# BMS_MCU.net
KiCad netlist of a schematic drawn in Altium Designer
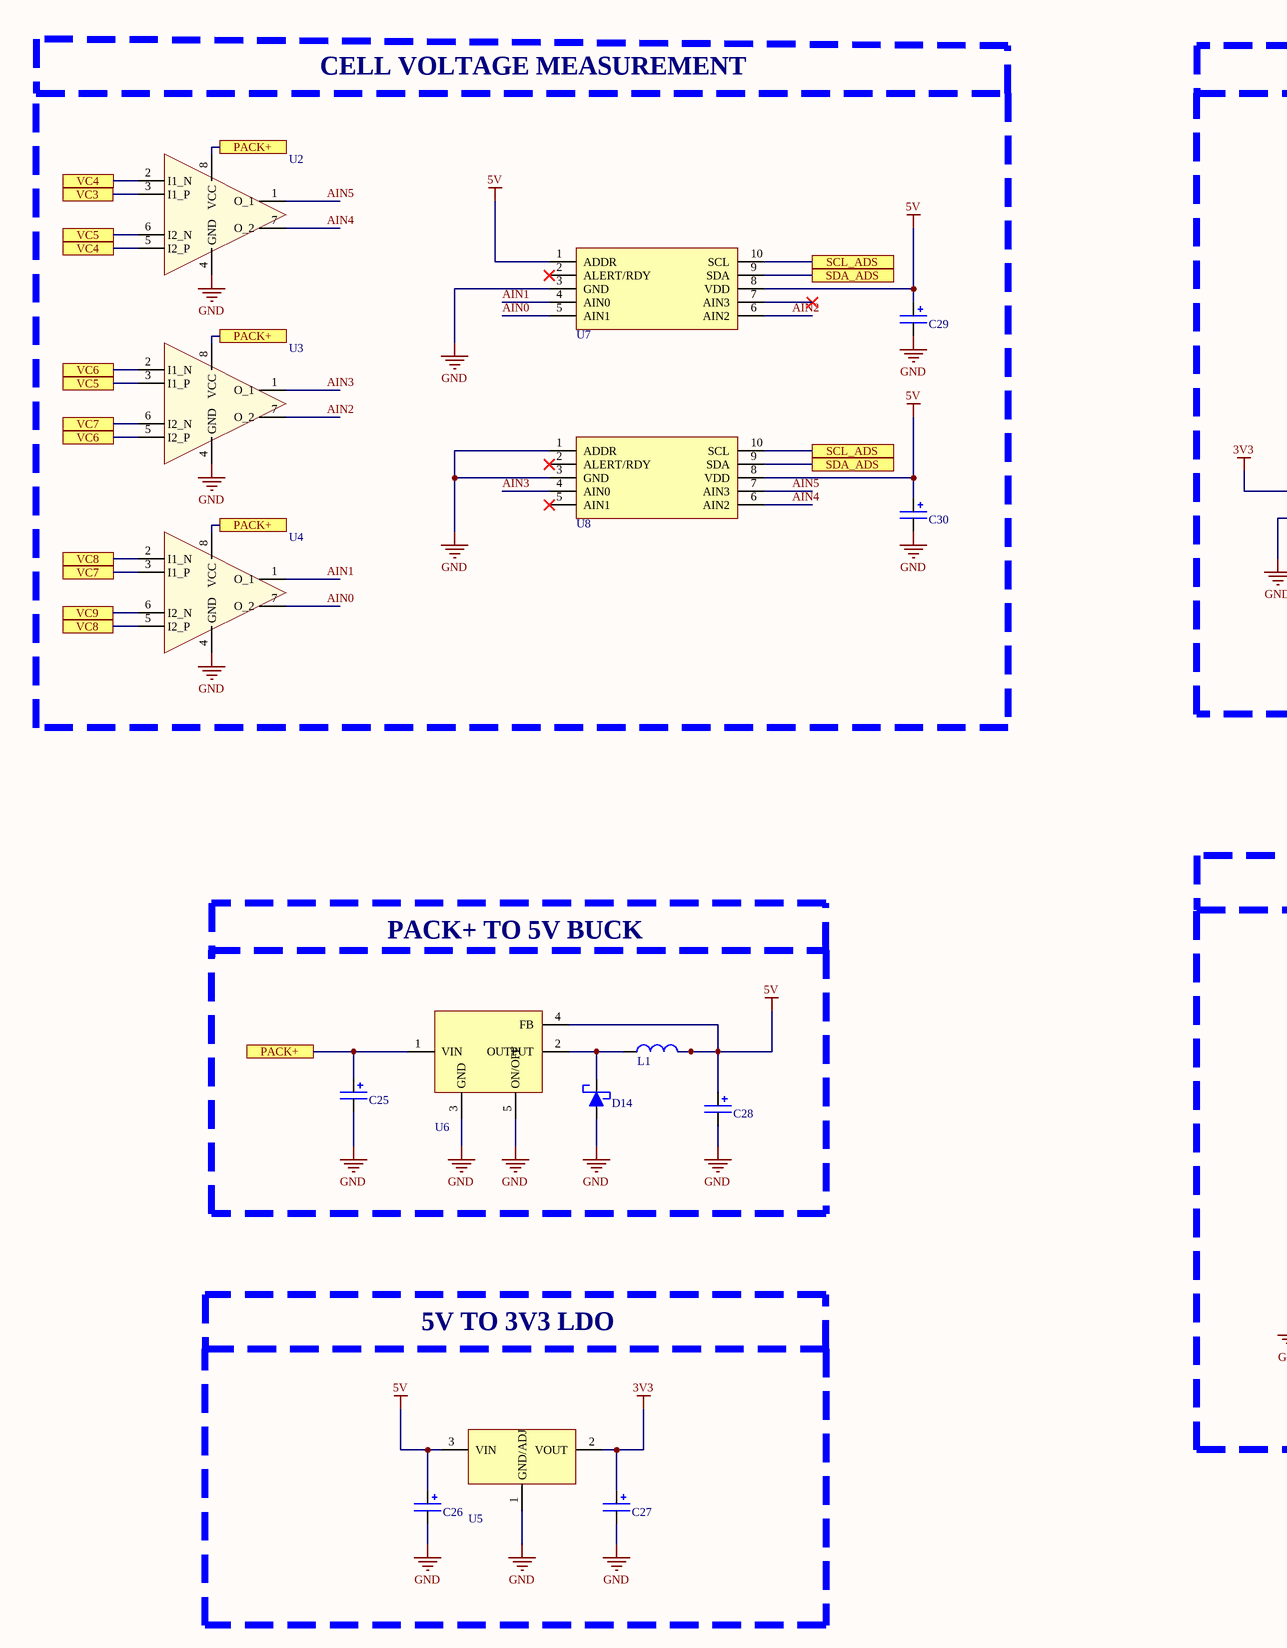
[diagram p0: BMS_MCU.SchDoc, left]
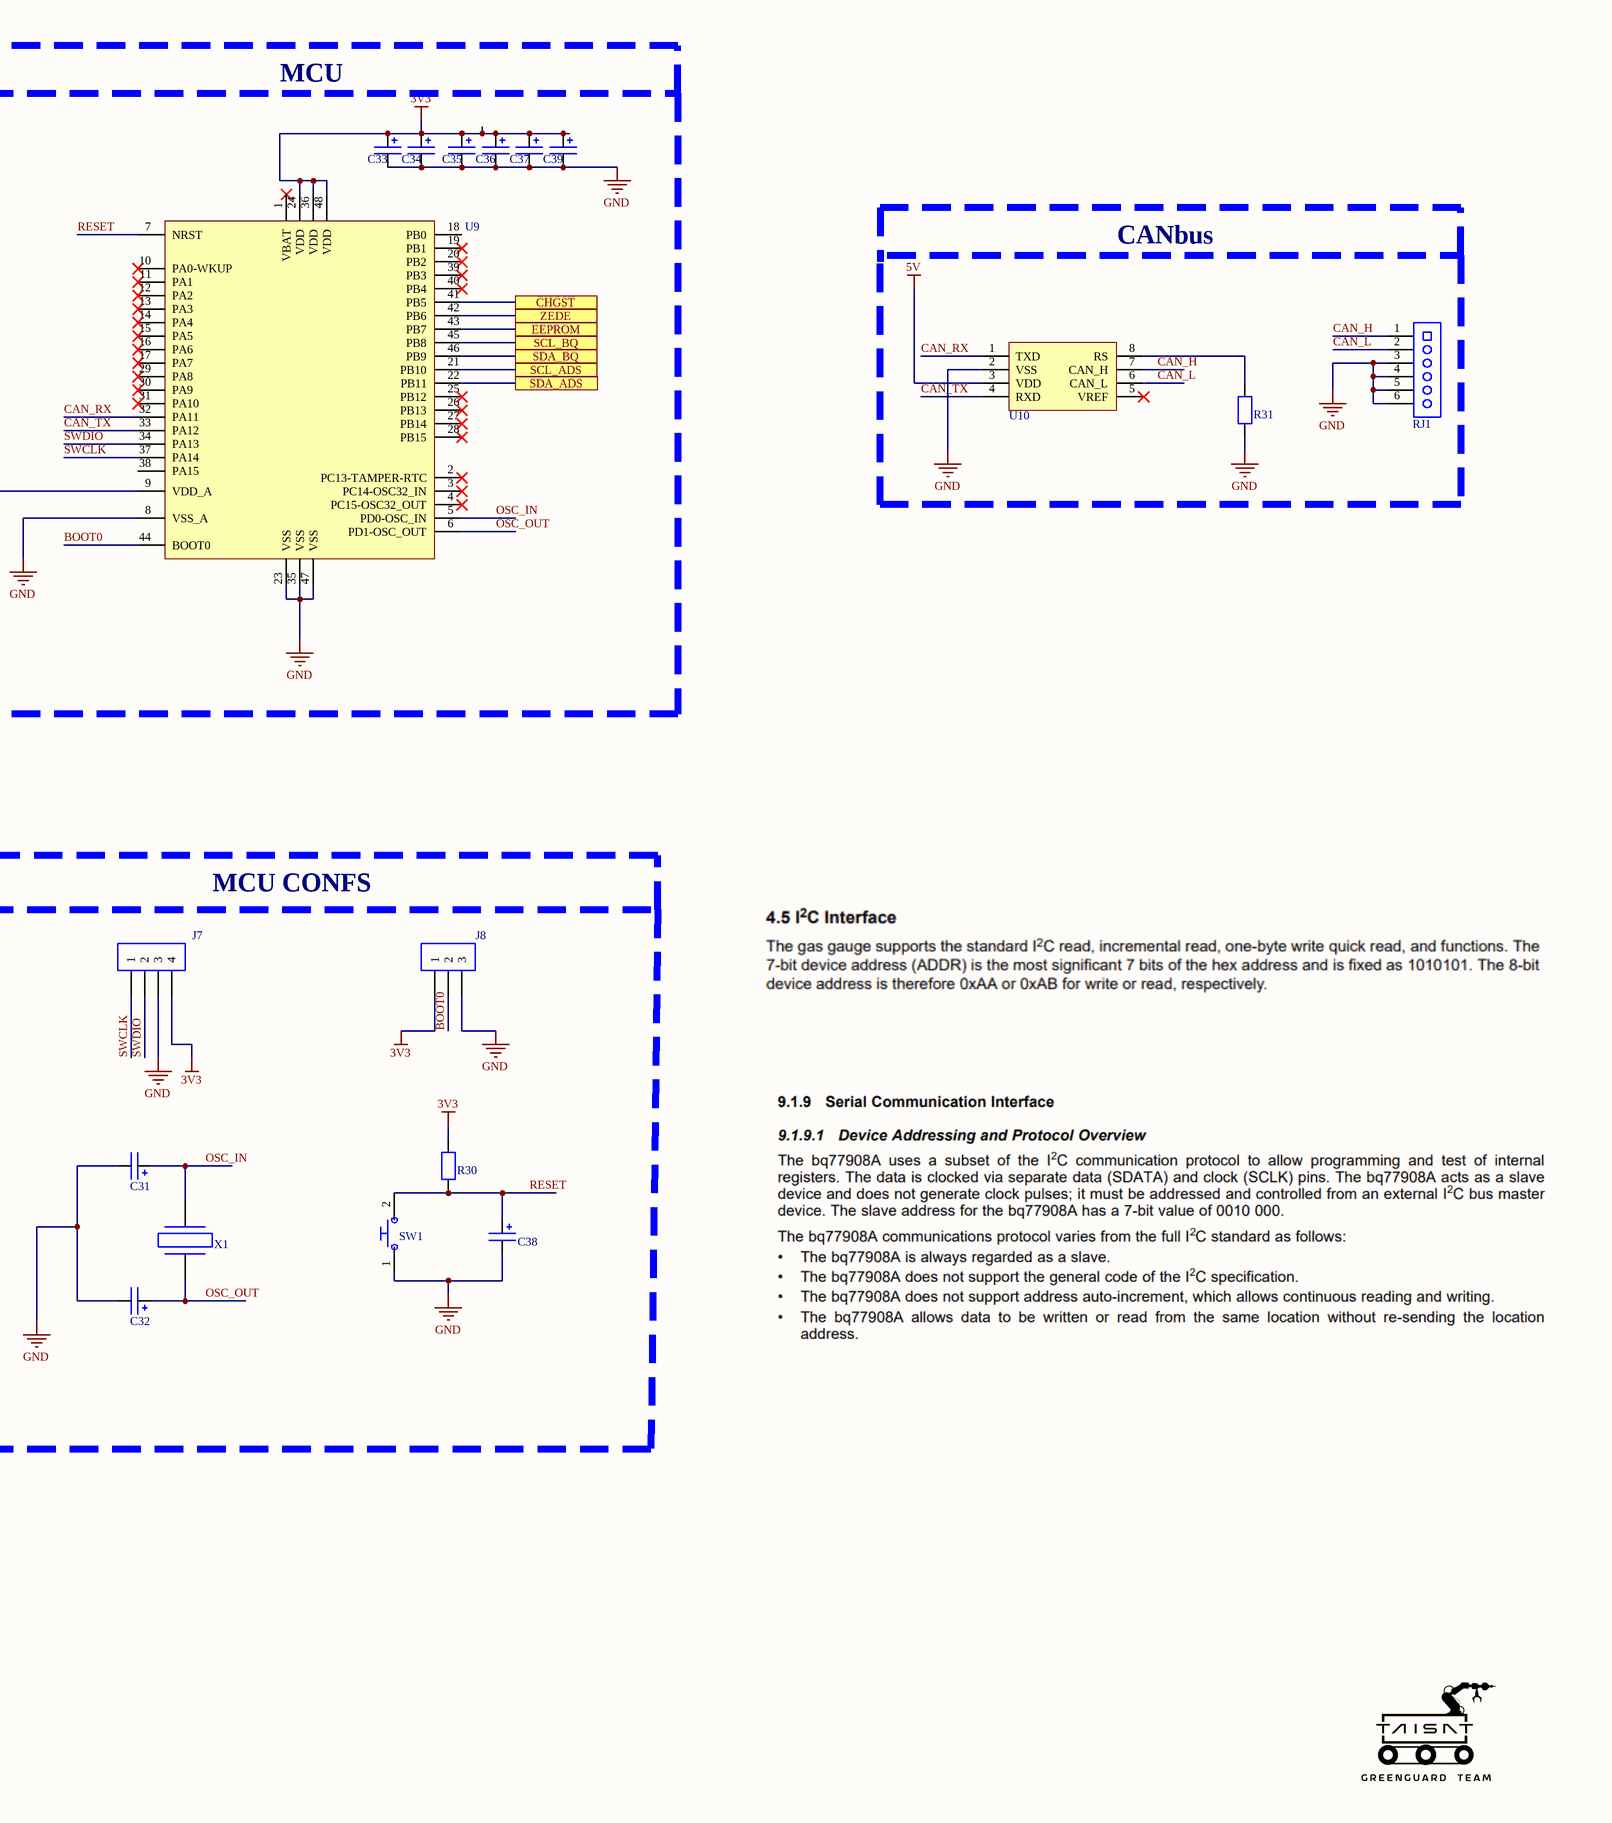
[diagram p1: BMS_MCU.SchDoc, right]

(export (version "E")
  (design (tool "Eeschema 10.0.6"))
  (components
    (comp (ref "C25")
      (value "100uF")
      (footprint "CAP 0603")
      (description "Multilayer Ceramic Capacitor")
      (fields
        (field (name "MANUFACTURER") "KEMET")
        (field (name "MANUFACTURER PART NUMBER") "C0603C103K5RACTU")
        (field (name "CREATED BY") "Kaptanyum")
      )
      (libsource (lib "Kaptanyums Lib") (part "CAP 0603"))
    )
    (comp (ref "C26")
      (value "100nF")
      (footprint "CAP 0603")
      (description "Multilayer Ceramic Capacitor")
      (fields
        (field (name "MANUFACTURER") "KEMET")
        (field (name "MANUFACTURER PART NUMBER") "C0603C103K5RACTU")
        (field (name "CREATED BY") "Kaptanyum")
      )
      (libsource (lib "Kaptanyums Lib") (part "CAP 0603"))
    )
    (comp (ref "C27")
      (value "22uF")
      (footprint "CAP 0603")
      (description "Multilayer Ceramic Capacitor")
      (fields
        (field (name "MANUFACTURER") "KEMET")
        (field (name "MANUFACTURER PART NUMBER") "C0603C103K5RACTU")
        (field (name "CREATED BY") "Kaptanyum")
      )
      (libsource (lib "Kaptanyums Lib") (part "CAP 0603"))
    )
    (comp (ref "C28")
      (value "330uF")
      (footprint "CAP 0603")
      (description "Multilayer Ceramic Capacitor")
      (fields
        (field (name "MANUFACTURER") "KEMET")
        (field (name "MANUFACTURER PART NUMBER") "C0603C103K5RACTU")
        (field (name "CREATED BY") "Kaptanyum")
      )
      (libsource (lib "Kaptanyums Lib") (part "CAP 0603"))
    )
    (comp (ref "C29")
      (value "0.1uF")
      (footprint "CAP 0603")
      (description "Multilayer Ceramic Capacitor")
      (fields
        (field (name "MANUFACTURER") "KEMET")
        (field (name "MANUFACTURER PART NUMBER") "C0603C103K5RACTU")
        (field (name "CREATED BY") "Kaptanyum")
      )
      (libsource (lib "Kaptanyums Lib") (part "CAP 0603"))
    )
    (comp (ref "C30")
      (value "0.1uF")
      (footprint "CAP 0603")
      (description "Multilayer Ceramic Capacitor")
      (fields
        (field (name "MANUFACTURER") "KEMET")
        (field (name "MANUFACTURER PART NUMBER") "C0603C103K5RACTU")
        (field (name "CREATED BY") "Kaptanyum")
      )
      (libsource (lib "Kaptanyums Lib") (part "CAP 0603"))
    )
    (comp (ref "C31")
      (value "0.1uF")
      (footprint "CAP 0603")
      (description "Multilayer Ceramic Capacitor")
      (fields
        (field (name "MANUFACTURER") "KEMET")
        (field (name "MANUFACTURER PART NUMBER") "C0603C103K5RACTU")
        (field (name "CREATED BY") "Kaptanyum")
      )
      (libsource (lib "Kaptanyums Lib") (part "CAP 0603"))
    )
    (comp (ref "C32")
      (value "0.1uF")
      (footprint "CAP 0603")
      (description "Multilayer Ceramic Capacitor")
      (fields
        (field (name "MANUFACTURER") "KEMET")
        (field (name "MANUFACTURER PART NUMBER") "C0603C103K5RACTU")
        (field (name "CREATED BY") "Kaptanyum")
      )
      (libsource (lib "Kaptanyums Lib") (part "CAP 0603"))
    )
    (comp (ref "C33")
      (value "0.1uF")
      (footprint "CAP 0603")
      (description "Multilayer Ceramic Capacitor")
      (fields
        (field (name "MANUFACTURER") "KEMET")
        (field (name "MANUFACTURER PART NUMBER") "C0603C103K5RACTU")
        (field (name "CREATED BY") "Kaptanyum")
      )
      (libsource (lib "Kaptanyums Lib") (part "CAP 0603"))
    )
    (comp (ref "C34")
      (value "0.1uF")
      (footprint "CAP 0603")
      (description "Multilayer Ceramic Capacitor")
      (fields
        (field (name "MANUFACTURER") "KEMET")
        (field (name "MANUFACTURER PART NUMBER") "C0603C103K5RACTU")
        (field (name "CREATED BY") "Kaptanyum")
      )
      (libsource (lib "Kaptanyums Lib") (part "CAP 0603"))
    )
    (comp (ref "C35")
      (value "0.1uF")
      (footprint "CAP 0603")
      (description "Multilayer Ceramic Capacitor")
      (fields
        (field (name "MANUFACTURER") "KEMET")
        (field (name "MANUFACTURER PART NUMBER") "C0603C103K5RACTU")
        (field (name "CREATED BY") "Kaptanyum")
      )
      (libsource (lib "Kaptanyums Lib") (part "CAP 0603"))
    )
    (comp (ref "C36")
      (value "0.1uF")
      (footprint "CAP 0603")
      (description "Multilayer Ceramic Capacitor")
      (fields
        (field (name "MANUFACTURER") "KEMET")
        (field (name "MANUFACTURER PART NUMBER") "C0603C103K5RACTU")
        (field (name "CREATED BY") "Kaptanyum")
      )
      (libsource (lib "Kaptanyums Lib") (part "CAP 0603"))
    )
    (comp (ref "C37")
      (value "0.1uF")
      (footprint "CAP 0603")
      (description "Multilayer Ceramic Capacitor")
      (fields
        (field (name "MANUFACTURER") "KEMET")
        (field (name "MANUFACTURER PART NUMBER") "C0603C103K5RACTU")
        (field (name "CREATED BY") "Kaptanyum")
      )
      (libsource (lib "Kaptanyums Lib") (part "CAP 0603"))
    )
    (comp (ref "C38")
      (value "0.1uF")
      (footprint "CAP 0603")
      (description "Multilayer Ceramic Capacitor")
      (fields
        (field (name "MANUFACTURER") "KEMET")
        (field (name "MANUFACTURER PART NUMBER") "C0603C103K5RACTU")
        (field (name "CREATED BY") "Kaptanyum")
      )
      (libsource (lib "Kaptanyums Lib") (part "CAP 0603"))
    )
    (comp (ref "C39")
      (value "0.1uF")
      (footprint "CAP 0603")
      (description "Multilayer Ceramic Capacitor")
      (fields
        (field (name "MANUFACTURER") "KEMET")
        (field (name "MANUFACTURER PART NUMBER") "C0603C103K5RACTU")
        (field (name "CREATED BY") "Kaptanyum")
      )
      (libsource (lib "Kaptanyums Lib") (part "CAP 0603"))
    )
    (comp (ref "D14")
      (value "1N5819HW-7-F")
      (footprint "SOD123")
      (description "Diode Schottky 40V")
      (fields (field (name "MANUFACTURER") "Diodes") (field (name "CREATED BY") "Kaptanyum"))
      (libsource (lib "Kaptanyums Lib") (part "1N5819HW-7-F"))
    )
    (comp (ref "J7")
      (value "146285-4")
      (footprint "HEADER 1x4")
      (description "Header for PCB")
      (fields
        (field (name "MANUFACTURER") "JST")
        (field (name "MANUFACTURER PART NUMBER") "B4B-XH-A(LF)(SN)")
        (field (name "CREATED BY") "Kaptanyum")
      )
      (libsource (lib "Kaptanyums Lib") (part "HEADER 1x4"))
    )
    (comp (ref "J8")
      (value "146285-3")
      (footprint "HEADER 1x3")
      (description "Header for PCB")
      (fields
        (field (name "MANUFACTURER") "JST")
        (field (name "MANUFACTURER PART NUMBER") "B4B-XH-A(LF)(SN)")
        (field (name "CREATED BY") "Kaptanyum")
      )
      (libsource (lib "Kaptanyums Lib") (part "HEADER 1x3"))
    )
    (comp (ref "L1")
      (value "330uH")
      (footprint "INDUCTOR SMD")
      (description "Inductor Power Shielded Wirewound")
      (fields
        (field (name "MANUFACTURER") "Bourns")
        (field (name "MANUFACTURER PART NUMBER") "SRR1260-330M")
        (field (name "CREATED BY") "Kaptanyum")
      )
      (libsource (lib "Kaptanyums Lib") (part "INDUCTOR SMD"))
    )
    (comp (ref "R30")
      (value "1K")
      (footprint "RESISTOR 0603")
      (description "SMD Chip Resistor")
      (fields
        (field (name "MANUFACTURER") "Yageo")
        (field (name "MANUFACTURER PART NUMBER") "AC0603FR-071KL")
        (field (name "CREATED BY") "Kaptanyum")
      )
      (libsource (lib "Kaptanyums Lib") (part "RES 0603"))
    )
    (comp (ref "R31")
      (value "10K")
      (footprint "RESISTOR 0603")
      (description "SMD Chip Resistor")
      (fields
        (field (name "MANUFACTURER") "Yageo")
        (field (name "MANUFACTURER PART NUMBER") "AC0603FR-071KL")
        (field (name "CREATED BY") "Kaptanyum")
      )
      (libsource (lib "Kaptanyums Lib") (part "RES 0603"))
    )
    (comp (ref "RJ1")
      (value "DS1133-03-S60BX")
      (footprint "RJ11,RJ12,RJ14,RJ25")
      (description "6P6C RJ11, RJ12, RJ14, RJ25")
      (libsource (lib "Schlib") (part "RJ14 SOCKET"))
    )
    (comp (ref "SW1")
      (value "DTSMF-31R")
      (footprint "SWITCH 6.00 x 3.5 - 2")
      (description "Switch 6mm x 3.5mm")
      (libsource (lib "Kaptanyums Lib") (part "DTSMF-31R"))
    )
    (comp (ref "U2")
      (value "TL3472CDR")
      (footprint "SOIC-8")
      (description "Op-Amp Gen 2-ch")
      (libsource (lib "Kaptanyums Lib") (part "TL3472CDR"))
    )
    (comp (ref "U3")
      (value "TL3472CDR")
      (footprint "SOIC-8")
      (description "Op-Amp Gen 2-ch")
      (libsource (lib "Kaptanyums Lib") (part "TL3472CDR"))
    )
    (comp (ref "U4")
      (value "TL3472CDR")
      (footprint "SOIC-8")
      (description "Op-Amp Gen 2-ch")
      (libsource (lib "Kaptanyums Lib") (part "TL3472CDR"))
    )
    (comp (ref "U5")
      (value "AMS1117-3V3")
      (footprint "SOT223-3")
      (description "Linear Voltage Regulator")
      (fields (field (name "CREATED BY") "Kaptanyum"))
      (libsource (lib "Kaptanyums Lib") (part "AMS1117-3V3"))
    )
    (comp (ref "U6")
      (value "LM2575-5V")
      (footprint "D2PAK-5")
      (description "Buck Regulator")
      (fields
        (field (name "MANUFACTURER") "TI National Semiconductor")
        (field (name "MANUFACTURER PART NUMBER") "LM2575SX-5.0/NOPB")
        (field (name "CREATED BY") "Kaptanyum")
      )
      (libsource (lib "Kaptanyums Lib") (part "LM2575-5V"))
    )
    (comp (ref "U7")
      (value "ADS1015")
      (footprint "VSSOP-10")
      (description "Quad Channel Single ADC")
      (fields
        (field (name "MANUFACTURER") "Texas Instruments")
        (field (name "MANUFACTURER PART NUMBER") "ADS1015IDGST")
        (field (name "CREATED BY") "Kaptanyum")
      )
      (libsource (lib "Kaptanyums Lib") (part "ADS1015"))
    )
    (comp (ref "U8")
      (value "ADS1015")
      (footprint "VSSOP-10")
      (description "Quad Channel Single ADC")
      (fields
        (field (name "MANUFACTURER") "Texas Instruments")
        (field (name "MANUFACTURER PART NUMBER") "ADS1015IDGST")
        (field (name "CREATED BY") "Kaptanyum")
      )
      (libsource (lib "Kaptanyums Lib") (part "ADS1015"))
    )
    (comp (ref "U9")
      (value "STM32F103x8")
      (footprint "LQFP48")
      (description "MCU 32-bit STM32F ARM Cortex M3")
      (fields
        (field (name "MANUFACTURER") "STMicroelectronics")
        (field (name "MANUFACTURER PART NUMBER") "STM32F103C6T6A")
        (field (name "CREATED BY") "Kaptanyum")
      )
      (libsource (lib "Kaptanyums Lib") (part "STM32F103x8"))
    )
    (comp (ref "U10")
      (value "MCP2551T-I")
      (footprint "SOIC-8")
      (description "CAN Transceiver")
      (fields
        (field (name "MANUFACTURER") "Microchip")
        (field (name "MANUFACTURER PART NUMBER") "MCP2551T-E/SN")
        (field (name "CREATED BY") "Kaptanyum")
      )
      (libsource (lib "Kaptanyums Lib") (part "MCP2551T-I"))
    )
    (comp (ref "X1")
      (value "CRYSTAL")
      (footprint "CRYSTAL THT")
      (description "8 MHZ DIP")
      (libsource (lib "Kaptanyums Lib") (part "CRYSTAL"))
    )
  )
  (nets
    (net (code "1") (name "/AIN0") (class "Default")
      (node (ref "U4") (pin "7") (pinfunction "O_2_7") (pintype "passive"))
      (node (ref "U7") (pin "5") (pinfunction "AIN1_5") (pintype "passive"))
    )
    (net (code "2") (name "/AIN1") (class "Default")
      (node (ref "U4") (pin "1") (pinfunction "O_1_1") (pintype "passive"))
      (node (ref "U7") (pin "4") (pinfunction "AIN0_4") (pintype "passive"))
    )
    (net (code "3") (name "/AIN2") (class "Default")
      (node (ref "U3") (pin "7") (pinfunction "O_2_7") (pintype "passive"))
      (node (ref "U7") (pin "6") (pinfunction "AIN2_6") (pintype "passive"))
    )
    (net (code "4") (name "/AIN3") (class "Default")
      (node (ref "U3") (pin "1") (pinfunction "O_1_1") (pintype "passive"))
      (node (ref "U8") (pin "4") (pinfunction "AIN0_4") (pintype "passive"))
    )
    (net (code "5") (name "/AIN4") (class "Default")
      (node (ref "U2") (pin "7") (pinfunction "O_2_7") (pintype "passive"))
      (node (ref "U8") (pin "6") (pinfunction "AIN2_6") (pintype "passive"))
    )
    (net (code "6") (name "/AIN5") (class "Default")
      (node (ref "U2") (pin "1") (pinfunction "O_1_1") (pintype "passive"))
      (node (ref "U8") (pin "7") (pinfunction "AIN3_7") (pintype "passive"))
    )
    (net (code "7") (name "/BOOT0") (class "Default")
      (node (ref "J8") (pin "2") (pinfunction "2_2") (pintype "passive"))
      (node (ref "U9") (pin "44") (pinfunction "BOOT0_44") (pintype "passive"))
    )
    (net (code "8") (name "/CAN_H") (class "Default")
      (node (ref "RJ1") (pin "1") (pinfunction "1_1") (pintype "passive"))
      (node (ref "U10") (pin "7") (pinfunction "CAN_H_7") (pintype "passive"))
    )
    (net (code "9") (name "/CAN_L") (class "Default")
      (node (ref "RJ1") (pin "2") (pinfunction "2_2") (pintype "passive"))
      (node (ref "U10") (pin "6") (pinfunction "CAN_L_6") (pintype "passive"))
    )
    (net (code "10") (name "/CAN_RX") (class "Default")
      (node (ref "U10") (pin "1") (pinfunction "TXD_1") (pintype "passive"))
      (node (ref "U9") (pin "32") (pinfunction "PA11_32") (pintype "passive"))
    )
    (net (code "11") (name "/CAN_TX") (class "Default")
      (node (ref "U10") (pin "4") (pinfunction "RXD_4") (pintype "passive"))
      (node (ref "U9") (pin "33") (pinfunction "PA12_33") (pintype "passive"))
    )
    (net (code "12") (name "/CHGST") (class "Default")
      (node (ref "U9") (pin "41") (pinfunction "PB5_41") (pintype "passive"))
    )
    (net (code "13") (name "/EEPROM") (class "Default")
      (node (ref "U9") (pin "43") (pinfunction "PB7_43") (pintype "passive"))
    )
    (net (code "14") (name "/OSC_IN") (class "Default")
      (node (ref "C31") (pin "1") (pinfunction "1_1") (pintype "passive"))
      (node (ref "U9") (pin "5") (pinfunction "PD0-OSC_IN_5") (pintype "passive"))
      (node (ref "X1") (pin "1") (pinfunction "1_1") (pintype "passive"))
    )
    (net (code "15") (name "/OSC_OUT") (class "Default")
      (node (ref "C32") (pin "1") (pinfunction "1_1") (pintype "passive"))
      (node (ref "U9") (pin "6") (pinfunction "PD1-OSC_OUT_6") (pintype "passive"))
      (node (ref "X1") (pin "2") (pinfunction "2_2") (pintype "passive"))
    )
    (net (code "16") (name "/PACK+") (class "Default")
      (node (ref "C25") (pin "1") (pinfunction "1_1") (pintype "passive"))
      (node (ref "U2") (pin "8") (pinfunction "VCC_8") (pintype "passive"))
      (node (ref "U3") (pin "8") (pinfunction "VCC_8") (pintype "passive"))
      (node (ref "U4") (pin "8") (pinfunction "VCC_8") (pintype "passive"))
      (node (ref "U6") (pin "1") (pinfunction "VIN_1") (pintype "passive"))
    )
    (net (code "17") (name "/RESET") (class "Default")
      (node (ref "C38") (pin "1") (pinfunction "1_1") (pintype "passive"))
      (node (ref "R30") (pin "1") (pinfunction "1_1") (pintype "passive"))
      (node (ref "SW1") (pin "2") (pinfunction "2_2") (pintype "passive"))
      (node (ref "U9") (pin "7") (pinfunction "NRST_7") (pintype "passive"))
    )
    (net (code "18") (name "/SCL_ADS") (class "Default")
      (node (ref "U7") (pin "10") (pinfunction "SCL_10") (pintype "passive"))
      (node (ref "U8") (pin "10") (pinfunction "SCL_10") (pintype "passive"))
      (node (ref "U9") (pin "21") (pinfunction "PB10_21") (pintype "passive"))
    )
    (net (code "19") (name "/SCL_BQ") (class "Default")
      (node (ref "U9") (pin "45") (pinfunction "PB8_45") (pintype "passive"))
    )
    (net (code "20") (name "/SDA_ADS") (class "Default")
      (node (ref "U7") (pin "9") (pinfunction "SDA_9") (pintype "passive"))
      (node (ref "U8") (pin "9") (pinfunction "SDA_9") (pintype "passive"))
      (node (ref "U9") (pin "22") (pinfunction "PB11_22") (pintype "passive"))
    )
    (net (code "21") (name "/SDA_BQ") (class "Default")
      (node (ref "U9") (pin "46") (pinfunction "PB9_46") (pintype "passive"))
    )
    (net (code "22") (name "/SWCLK") (class "Default")
      (node (ref "J7") (pin "1") (pinfunction "1_1") (pintype "passive"))
      (node (ref "U9") (pin "37") (pinfunction "PA14_37") (pintype "passive"))
    )
    (net (code "23") (name "/SWDIO") (class "Default")
      (node (ref "J7") (pin "2") (pinfunction "2_2") (pintype "passive"))
      (node (ref "U9") (pin "34") (pinfunction "PA13_34") (pintype "passive"))
    )
    (net (code "24") (name "/VC3") (class "Default")
      (node (ref "U2") (pin "3") (pinfunction "I1_P_3") (pintype "passive"))
    )
    (net (code "25") (name "/VC4") (class "Default")
      (node (ref "U2") (pin "2") (pinfunction "I1_N_2") (pintype "passive"))
      (node (ref "U2") (pin "5") (pinfunction "I2_P_5") (pintype "passive"))
    )
    (net (code "26") (name "/VC5") (class "Default")
      (node (ref "U2") (pin "6") (pinfunction "I2_N_6") (pintype "passive"))
      (node (ref "U3") (pin "3") (pinfunction "I1_P_3") (pintype "passive"))
    )
    (net (code "27") (name "/VC6") (class "Default")
      (node (ref "U3") (pin "2") (pinfunction "I1_N_2") (pintype "passive"))
      (node (ref "U3") (pin "5") (pinfunction "I2_P_5") (pintype "passive"))
    )
    (net (code "28") (name "/VC7") (class "Default")
      (node (ref "U3") (pin "6") (pinfunction "I2_N_6") (pintype "passive"))
      (node (ref "U4") (pin "3") (pinfunction "I1_P_3") (pintype "passive"))
    )
    (net (code "29") (name "/VC8") (class "Default")
      (node (ref "U4") (pin "2") (pinfunction "I1_N_2") (pintype "passive"))
      (node (ref "U4") (pin "5") (pinfunction "I2_P_5") (pintype "passive"))
    )
    (net (code "30") (name "/VC9") (class "Default")
      (node (ref "U4") (pin "6") (pinfunction "I2_N_6") (pintype "passive"))
    )
    (net (code "31") (name "/ZEDE") (class "Default")
      (node (ref "U9") (pin "42") (pinfunction "PB6_42") (pintype "passive"))
    )
    (net (code "32") (name "3V3") (class "Default")
      (node (ref "C27") (pin "1") (pinfunction "1_1") (pintype "passive"))
      (node (ref "C33") (pin "1") (pinfunction "1_1") (pintype "passive"))
      (node (ref "C34") (pin "1") (pinfunction "1_1") (pintype "passive"))
      (node (ref "C35") (pin "1") (pinfunction "1_1") (pintype "passive"))
      (node (ref "C36") (pin "1") (pinfunction "1_1") (pintype "passive"))
      (node (ref "C37") (pin "1") (pinfunction "1_1") (pintype "passive"))
      (node (ref "C39") (pin "1") (pinfunction "1_1") (pintype "passive"))
      (node (ref "J7") (pin "4") (pinfunction "4_4") (pintype "passive"))
      (node (ref "J8") (pin "1") (pinfunction "1_1") (pintype "passive"))
      (node (ref "R30") (pin "2") (pinfunction "2_2") (pintype "passive"))
      (node (ref "U5") (pin "2") (pinfunction "VOUT_2") (pintype "passive"))
      (node (ref "U9") (pin "24") (pinfunction "VDD_24") (pintype "passive"))
      (node (ref "U9") (pin "36") (pinfunction "VDD_36") (pintype "passive"))
      (node (ref "U9") (pin "48") (pinfunction "VDD_48") (pintype "passive"))
      (node (ref "U9") (pin "9") (pinfunction "VDD_A_9") (pintype "passive"))
    )
    (net (code "33") (name "5V") (class "Default")
      (node (ref "C26") (pin "1") (pinfunction "1_1") (pintype "passive"))
      (node (ref "C28") (pin "1") (pinfunction "1_1") (pintype "passive"))
      (node (ref "C29") (pin "1") (pinfunction "1_1") (pintype "passive"))
      (node (ref "C30") (pin "1") (pinfunction "1_1") (pintype "passive"))
      (node (ref "L1") (pin "2") (pinfunction "2_2") (pintype "passive"))
      (node (ref "U10") (pin "3") (pinfunction "VDD_3") (pintype "passive"))
      (node (ref "U5") (pin "3") (pinfunction "VIN_3") (pintype "passive"))
      (node (ref "U6") (pin "4") (pinfunction "FB_4") (pintype "passive"))
      (node (ref "U7") (pin "1") (pinfunction "ADDR_1") (pintype "passive"))
      (node (ref "U7") (pin "8") (pinfunction "VDD_8") (pintype "passive"))
      (node (ref "U8") (pin "8") (pinfunction "VDD_8") (pintype "passive"))
    )
    (net (code "34") (name "GND") (class "Default")
      (node (ref "C25") (pin "2") (pinfunction "2_2") (pintype "passive"))
      (node (ref "C26") (pin "2") (pinfunction "2_2") (pintype "passive"))
      (node (ref "C27") (pin "2") (pinfunction "2_2") (pintype "passive"))
      (node (ref "C28") (pin "2") (pinfunction "2_2") (pintype "passive"))
      (node (ref "C29") (pin "2") (pinfunction "2_2") (pintype "passive"))
      (node (ref "C30") (pin "2") (pinfunction "2_2") (pintype "passive"))
      (node (ref "C31") (pin "2") (pinfunction "2_2") (pintype "passive"))
      (node (ref "C32") (pin "2") (pinfunction "2_2") (pintype "passive"))
      (node (ref "C33") (pin "2") (pinfunction "2_2") (pintype "passive"))
      (node (ref "C34") (pin "2") (pinfunction "2_2") (pintype "passive"))
      (node (ref "C35") (pin "2") (pinfunction "2_2") (pintype "passive"))
      (node (ref "C36") (pin "2") (pinfunction "2_2") (pintype "passive"))
      (node (ref "C37") (pin "2") (pinfunction "2_2") (pintype "passive"))
      (node (ref "C38") (pin "2") (pinfunction "2_2") (pintype "passive"))
      (node (ref "C39") (pin "2") (pinfunction "2_2") (pintype "passive"))
      (node (ref "D14") (pin "2") (pinfunction "2_2") (pintype "passive"))
      (node (ref "J7") (pin "3") (pinfunction "3_3") (pintype "passive"))
      (node (ref "J8") (pin "3") (pinfunction "3_3") (pintype "passive"))
      (node (ref "R31") (pin "1") (pinfunction "1_1") (pintype "passive"))
      (node (ref "RJ1") (pin "3") (pinfunction "3_3") (pintype "passive"))
      (node (ref "RJ1") (pin "4") (pinfunction "4_4") (pintype "passive"))
      (node (ref "RJ1") (pin "5") (pinfunction "5_5") (pintype "passive"))
      (node (ref "RJ1") (pin "6") (pinfunction "6_6") (pintype "passive"))
      (node (ref "SW1") (pin "1") (pinfunction "1_1") (pintype "passive"))
      (node (ref "U10") (pin "2") (pinfunction "VSS_2") (pintype "passive"))
      (node (ref "U2") (pin "4") (pinfunction "GND_4") (pintype "passive"))
      (node (ref "U3") (pin "4") (pinfunction "GND_4") (pintype "passive"))
      (node (ref "U4") (pin "4") (pinfunction "GND_4") (pintype "passive"))
      (node (ref "U5") (pin "1") (pinfunction "GND/ADJ_1") (pintype "passive"))
      (node (ref "U6") (pin "3") (pinfunction "GND_3") (pintype "passive"))
      (node (ref "U6") (pin "5") (pinfunction "ON/OFF_5") (pintype "passive"))
      (node (ref "U7") (pin "3") (pinfunction "GND_3") (pintype "passive"))
      (node (ref "U8") (pin "1") (pinfunction "ADDR_1") (pintype "passive"))
      (node (ref "U8") (pin "3") (pinfunction "GND_3") (pintype "passive"))
      (node (ref "U9") (pin "23") (pinfunction "VSS_23") (pintype "passive"))
      (node (ref "U9") (pin "35") (pinfunction "VSS_35") (pintype "passive"))
      (node (ref "U9") (pin "47") (pinfunction "VSS_47") (pintype "passive"))
      (node (ref "U9") (pin "8") (pinfunction "VSS_A_8") (pintype "passive"))
    )
    (net (code "35") (name "Net-(U6-OUTPUT)") (class "Default")
      (node (ref "D14") (pin "1") (pinfunction "1_1") (pintype "passive"))
      (node (ref "L1") (pin "1") (pinfunction "1_1") (pintype "passive"))
      (node (ref "U6") (pin "2") (pinfunction "OUTPUT_2") (pintype "passive"))
    )
    (net (code "36") (name "Net-(U10-RS)") (class "Default")
      (node (ref "R31") (pin "2") (pinfunction "2_2") (pintype "passive"))
      (node (ref "U10") (pin "8") (pinfunction "RS_8") (pintype "passive"))
    )
    (net (code "37") (name "unconnected-(U7-AIN3-Pad7)") (class "Default")
      (node (ref "U7") (pin "7") (pinfunction "AIN3_7") (pintype "passive+no_connect"))
    )
    (net (code "38") (name "unconnected-(U7-ALERT{slash}RDY-Pad2)") (class "Default")
      (node (ref "U7") (pin "2") (pinfunction "ALERT/RDY_2") (pintype "passive+no_connect"))
    )
    (net (code "39") (name "unconnected-(U8-AIN1-Pad5)") (class "Default")
      (node (ref "U8") (pin "5") (pinfunction "AIN1_5") (pintype "passive+no_connect"))
    )
    (net (code "40") (name "unconnected-(U8-ALERT{slash}RDY-Pad2)") (class "Default")
      (node (ref "U8") (pin "2") (pinfunction "ALERT/RDY_2") (pintype "passive+no_connect"))
    )
    (net (code "41") (name "unconnected-(U9-PA0-WKUP-Pad10)") (class "Default")
      (node (ref "U9") (pin "10") (pinfunction "PA0-WKUP_10") (pintype "passive+no_connect"))
    )
    (net (code "42") (name "unconnected-(U9-PA1-Pad11)") (class "Default")
      (node (ref "U9") (pin "11") (pinfunction "PA1_11") (pintype "passive+no_connect"))
    )
    (net (code "43") (name "unconnected-(U9-PA2-Pad12)") (class "Default")
      (node (ref "U9") (pin "12") (pinfunction "PA2_12") (pintype "passive+no_connect"))
    )
    (net (code "44") (name "unconnected-(U9-PA3-Pad13)") (class "Default")
      (node (ref "U9") (pin "13") (pinfunction "PA3_13") (pintype "passive+no_connect"))
    )
    (net (code "45") (name "unconnected-(U9-PA4-Pad14)") (class "Default")
      (node (ref "U9") (pin "14") (pinfunction "PA4_14") (pintype "passive+no_connect"))
    )
    (net (code "46") (name "unconnected-(U9-PA5-Pad15)") (class "Default")
      (node (ref "U9") (pin "15") (pinfunction "PA5_15") (pintype "passive+no_connect"))
    )
    (net (code "47") (name "unconnected-(U9-PA6-Pad16)") (class "Default")
      (node (ref "U9") (pin "16") (pinfunction "PA6_16") (pintype "passive+no_connect"))
    )
    (net (code "48") (name "unconnected-(U9-PA7-Pad17)") (class "Default")
      (node (ref "U9") (pin "17") (pinfunction "PA7_17") (pintype "passive+no_connect"))
    )
    (net (code "49") (name "unconnected-(U9-PA8-Pad29)") (class "Default")
      (node (ref "U9") (pin "29") (pinfunction "PA8_29") (pintype "passive+no_connect"))
    )
    (net (code "50") (name "unconnected-(U9-PA9-Pad30)") (class "Default")
      (node (ref "U9") (pin "30") (pinfunction "PA9_30") (pintype "passive+no_connect"))
    )
    (net (code "51") (name "unconnected-(U9-PA10-Pad31)") (class "Default")
      (node (ref "U9") (pin "31") (pinfunction "PA10_31") (pintype "passive+no_connect"))
    )
    (net (code "52") (name "unconnected-(U9-PA15-Pad38)") (class "Default")
      (node (ref "U9") (pin "38") (pinfunction "PA15_38") (pintype "passive"))
    )
    (net (code "53") (name "unconnected-(U9-PB0-Pad18)") (class "Default")
      (node (ref "U9") (pin "18") (pinfunction "PB0_18") (pintype "passive"))
    )
    (net (code "54") (name "unconnected-(U9-PB1-Pad19)") (class "Default")
      (node (ref "U9") (pin "19") (pinfunction "PB1_19") (pintype "passive+no_connect"))
    )
    (net (code "55") (name "unconnected-(U9-PB2-Pad20)") (class "Default")
      (node (ref "U9") (pin "20") (pinfunction "PB2_20") (pintype "passive+no_connect"))
    )
    (net (code "56") (name "unconnected-(U9-PB3-Pad39)") (class "Default")
      (node (ref "U9") (pin "39") (pinfunction "PB3_39") (pintype "passive+no_connect"))
    )
    (net (code "57") (name "unconnected-(U9-PB4-Pad40)") (class "Default")
      (node (ref "U9") (pin "40") (pinfunction "PB4_40") (pintype "passive+no_connect"))
    )
    (net (code "58") (name "unconnected-(U9-PB12-Pad25)") (class "Default")
      (node (ref "U9") (pin "25") (pinfunction "PB12_25") (pintype "passive+no_connect"))
    )
    (net (code "59") (name "unconnected-(U9-PB13-Pad26)") (class "Default")
      (node (ref "U9") (pin "26") (pinfunction "PB13_26") (pintype "passive+no_connect"))
    )
    (net (code "60") (name "unconnected-(U9-PB14-Pad27)") (class "Default")
      (node (ref "U9") (pin "27") (pinfunction "PB14_27") (pintype "passive+no_connect"))
    )
    (net (code "61") (name "unconnected-(U9-PB15-Pad28)") (class "Default")
      (node (ref "U9") (pin "28") (pinfunction "PB15_28") (pintype "passive+no_connect"))
    )
    (net (code "62") (name "unconnected-(U9-PC13-TAMPER-RTC-Pad2)") (class "Default")
      (node (ref "U9") (pin "2") (pinfunction "PC13-TAMPER-RTC_2") (pintype "passive+no_connect"))
    )
    (net (code "63") (name "unconnected-(U9-PC14-OSC32_IN-Pad3)") (class "Default")
      (node (ref "U9") (pin "3") (pinfunction "PC14-OSC32_IN_3") (pintype "passive+no_connect"))
    )
    (net (code "64") (name "unconnected-(U9-PC15-OSC32_OUT-Pad4)") (class "Default")
      (node (ref "U9") (pin "4") (pinfunction "PC15-OSC32_OUT_4") (pintype "passive+no_connect"))
    )
    (net (code "65") (name "unconnected-(U9-VBAT-Pad1)") (class "Default")
      (node (ref "U9") (pin "1") (pinfunction "VBAT_1") (pintype "passive+no_connect"))
    )
    (net (code "66") (name "unconnected-(U10-VREF-Pad5)") (class "Default")
      (node (ref "U10") (pin "5") (pinfunction "VREF_5") (pintype "passive+no_connect"))
    )
  )
)
